# LATCHING_CIRCUITS.net
KiCad netlist of a schematic drawn in Altium Designer
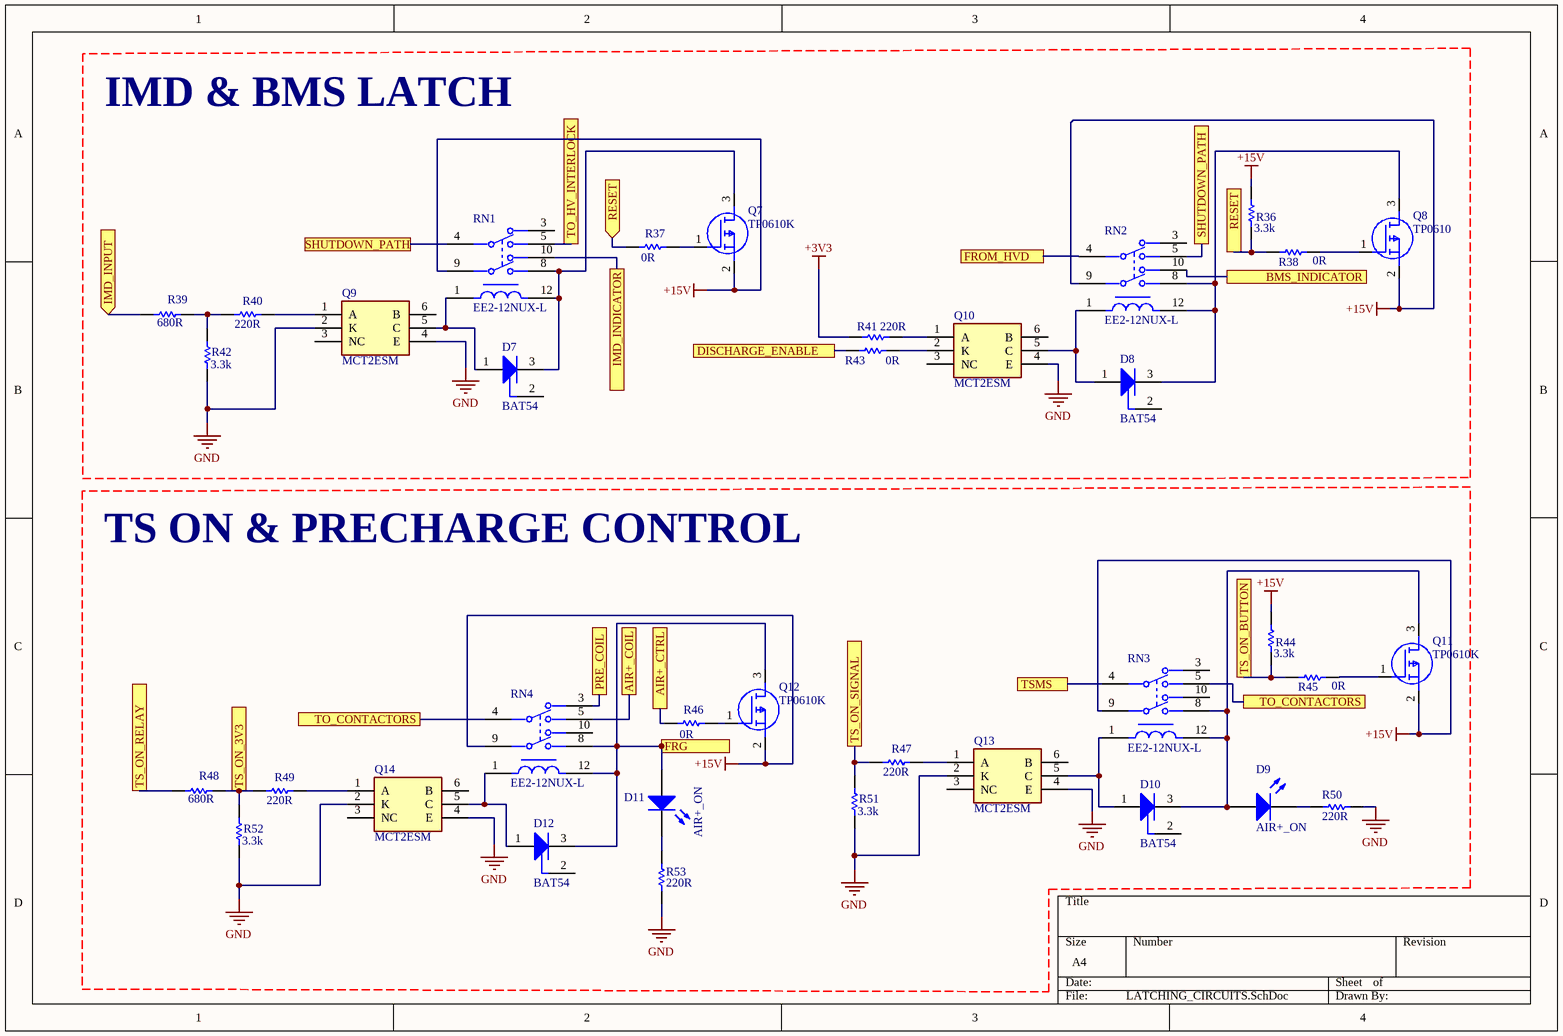
[diagram p0: LATCHING_CIRCUITS.SchDoc]

(export (version "E")
  (design (tool "Eeschema 10.0.6"))
  (components
    (comp (ref "D7")
      (value "BAT54")
      (footprint "INF-SOT23_N")
      (description "Silicon Schottky Diode, SOT23, Reel, Green")
      (fields (field (name "MANUFACTURER") "Infineon"))
      (libsource (lib "Schlib1") (part "CMP-1182-00010-1"))
    )
    (comp (ref "D8")
      (value "BAT54")
      (footprint "INF-SOT23_N")
      (description "Silicon Schottky Diode, SOT23, Reel, Green")
      (fields (field (name "MANUFACTURER") "Infineon"))
      (libsource (lib "Schlib1") (part "CMP-1182-00010-1"))
    )
    (comp (ref "D9")
      (value "AIR+_ON")
      (footprint "3.2X1.6X1.1")
      (description "Typical RED, GREEN, YELLOW, AMBER GaAs LED")
      (fields (field (name "PUBLISHER") "Altium Limited"))
      (libsource (lib "Miscellaneous Devices") (part "LED2"))
    )
    (comp (ref "D10")
      (value "BAT54")
      (footprint "INF-SOT23_N")
      (description "Silicon Schottky Diode, SOT23, Reel, Green")
      (fields (field (name "MANUFACTURER") "Infineon"))
      (libsource (lib "Schlib1") (part "CMP-1182-00010-1"))
    )
    (comp (ref "D11")
      (value "AIR+_ON")
      (footprint "3.2X1.6X1.1")
      (description "Typical RED, GREEN, YELLOW, AMBER GaAs LED")
      (fields (field (name "PUBLISHER") "Altium Limited"))
      (libsource (lib "Miscellaneous Devices") (part "LED2"))
    )
    (comp (ref "D12")
      (value "BAT54")
      (footprint "INF-SOT23_N")
      (description "Silicon Schottky Diode, SOT23, Reel, Green")
      (fields (field (name "MANUFACTURER") "Infineon"))
      (libsource (lib "Schlib1") (part "CMP-1182-00010-1"))
    )
    (comp (ref "Q7")
      (value "TP0610K")
      (footprint "SamacSys:SOT96P240X110-3N")
      (description "MOSFET (P-Channel)")
      (fields
        (field (name "MANUFACTURER_PART_NUMBER") "DMP3125L-7")
        (field (name "MOUSER PART NUMBER") "621-DMP3125L-7")
      )
      (libsource (lib "*") (part "DMP3125L-7"))
    )
    (comp (ref "Q8")
      (value "TP0610")
      (footprint "SamacSys:SOT96P240X110-3N")
      (description "MOSFET (P-Channel)")
      (fields
        (field (name "MANUFACTURER_PART_NUMBER") "DMP3125L-7")
        (field (name "MOUSER PART NUMBER") "621-DMP3125L-7")
      )
      (libsource (lib "*") (part "DMP3125L-7"))
    )
    (comp (ref "Q9")
      (value "MCT2ESM")
      (footprint "SOT254P916X480-6N")
      (description "Phototransistor")
      (fields (field (name "MOUSER PART NUMBER") "512-MCT2ESM"))
      (libsource (lib "SamacSys") (part "MCT2ESM"))
    )
    (comp (ref "Q10")
      (value "MCT2ESM")
      (footprint "SOT254P916X480-6N")
      (description "Phototransistor")
      (fields (field (name "MOUSER PART NUMBER") "512-MCT2ESM"))
      (libsource (lib "SamacSys") (part "MCT2ESM"))
    )
    (comp (ref "Q11")
      (value "TP0610K")
      (footprint "SamacSys:SOT96P240X110-3N")
      (description "MOSFET (P-Channel)")
      (fields
        (field (name "MANUFACTURER_PART_NUMBER") "DMP3125L-7")
        (field (name "MOUSER PART NUMBER") "621-DMP3125L-7")
      )
      (libsource (lib "*") (part "DMP3125L-7"))
    )
    (comp (ref "Q12")
      (value "TP0610K")
      (footprint "SamacSys:SOT96P240X110-3N")
      (description "MOSFET (P-Channel)")
      (fields
        (field (name "MANUFACTURER_PART_NUMBER") "DMP3125L-7")
        (field (name "MOUSER PART NUMBER") "621-DMP3125L-7")
      )
      (libsource (lib "*") (part "DMP3125L-7"))
    )
    (comp (ref "Q13")
      (value "MCT2ESM")
      (footprint "SOT254P916X480-6N")
      (description "Phototransistor")
      (fields (field (name "MOUSER PART NUMBER") "512-MCT2ESM"))
      (libsource (lib "SamacSys") (part "MCT2ESM"))
    )
    (comp (ref "Q14")
      (value "MCT2ESM")
      (footprint "SOT254P916X480-6N")
      (description "Phototransistor")
      (fields (field (name "MOUSER PART NUMBER") "512-MCT2ESM"))
      (libsource (lib "SamacSys") (part "MCT2ESM"))
    )
    (comp (ref "R36")
      (value "3.3k")
      (footprint "RESC3216X60X45NL10T20 - duplicate")
      (fields (field (name "PART NUMBER") "CRCW120647K0FKEA") (field (name "MANUFACTURER") "Vishay Dale"))
      (libsource (lib "Schlib1") (part "CMP-2003-02213-1"))
    )
    (comp (ref "R37")
      (value "0R")
      (footprint "RESC3216X60X45NL10T20 - duplicate")
      (fields (field (name "PART NUMBER") "CRCW120647K0FKEA") (field (name "MANUFACTURER") "Vishay Dale"))
      (libsource (lib "Schlib1") (part "CMP-2003-02213-1"))
    )
    (comp (ref "R38")
      (value "0R")
      (footprint "RESC3216X60X45NL10T20 - duplicate")
      (fields (field (name "PART NUMBER") "CRCW120647K0FKEA") (field (name "MANUFACTURER") "Vishay Dale"))
      (libsource (lib "Schlib1") (part "CMP-2003-02213-1"))
    )
    (comp (ref "R39")
      (value "680R")
      (footprint "RESC3216X60X45NL10T20 - duplicate")
      (fields (field (name "PART NUMBER") "CRCW120647K0FKEA") (field (name "MANUFACTURER") "Vishay Dale"))
      (libsource (lib "Schlib1") (part "CMP-2003-02213-1"))
    )
    (comp (ref "R40")
      (value "220R")
      (footprint "RESC3216X60X45NL10T20 - duplicate")
      (fields (field (name "PART NUMBER") "CRCW120647K0FKEA") (field (name "MANUFACTURER") "Vishay Dale"))
      (libsource (lib "Schlib1") (part "CMP-2003-02213-1"))
    )
    (comp (ref "R41")
      (value "220R")
      (footprint "RESC3216X60X45NL10T20 - duplicate")
      (fields (field (name "PART NUMBER") "CRCW120647K0FKEA") (field (name "MANUFACTURER") "Vishay Dale"))
      (libsource (lib "Schlib1") (part "CMP-2003-02213-1"))
    )
    (comp (ref "R42")
      (value "3.3k")
      (footprint "RESC3216X60X45NL10T20 - duplicate")
      (fields (field (name "PART NUMBER") "CRCW120647K0FKEA") (field (name "MANUFACTURER") "Vishay Dale"))
      (libsource (lib "Schlib1") (part "CMP-2003-02213-1"))
    )
    (comp (ref "R43")
      (value "0R")
      (footprint "RESC3216X60X45NL10T20 - duplicate")
      (fields (field (name "PART NUMBER") "CRCW120647K0FKEA") (field (name "MANUFACTURER") "Vishay Dale"))
      (libsource (lib "Schlib1") (part "CMP-2003-02213-1"))
    )
    (comp (ref "R44")
      (value "3.3k")
      (footprint "RESC3216X60X45NL10T20 - duplicate")
      (fields (field (name "PART NUMBER") "CRCW120647K0FKEA") (field (name "MANUFACTURER") "Vishay Dale"))
      (libsource (lib "Schlib1") (part "CMP-2003-02213-1"))
    )
    (comp (ref "R45")
      (value "0R")
      (footprint "RESC3216X60X45NL10T20 - duplicate")
      (fields (field (name "PART NUMBER") "CRCW120647K0FKEA") (field (name "MANUFACTURER") "Vishay Dale"))
      (libsource (lib "Schlib1") (part "CMP-2003-02213-1"))
    )
    (comp (ref "R46")
      (value "0R")
      (footprint "RESC3216X60X45NL10T20 - duplicate")
      (fields (field (name "PART NUMBER") "CRCW120647K0FKEA") (field (name "MANUFACTURER") "Vishay Dale"))
      (libsource (lib "Schlib1") (part "CMP-2003-02213-1"))
    )
    (comp (ref "R47")
      (value "220R")
      (footprint "RESC3216X60X45NL10T20 - duplicate")
      (fields (field (name "PART NUMBER") "CRCW120647K0FKEA") (field (name "MANUFACTURER") "Vishay Dale"))
      (libsource (lib "Schlib1") (part "CMP-2003-02213-1"))
    )
    (comp (ref "R48")
      (value "680R")
      (footprint "RESC3216X60X45NL10T20 - duplicate")
      (fields (field (name "PART NUMBER") "CRCW120647K0FKEA") (field (name "MANUFACTURER") "Vishay Dale"))
      (libsource (lib "Schlib1") (part "CMP-2003-02213-1"))
    )
    (comp (ref "R49")
      (value "220R")
      (footprint "RESC3216X60X45NL10T20 - duplicate")
      (fields (field (name "PART NUMBER") "CRCW120647K0FKEA") (field (name "MANUFACTURER") "Vishay Dale"))
      (libsource (lib "Schlib1") (part "CMP-2003-02213-1"))
    )
    (comp (ref "R50")
      (value "220R")
      (footprint "RESC3216X60X45NL10T20 - duplicate")
      (fields (field (name "PART NUMBER") "CRCW120647K0FKEA") (field (name "MANUFACTURER") "Vishay Dale"))
      (libsource (lib "Regular_used_components_2D_Symbol") (part "CMP-2003-02213-1"))
    )
    (comp (ref "R51")
      (value "3.3k")
      (footprint "RESC3216X60X45NL10T20 - duplicate")
      (fields (field (name "PART NUMBER") "CRCW120647K0FKEA") (field (name "MANUFACTURER") "Vishay Dale"))
      (libsource (lib "Schlib1") (part "CMP-2003-02213-1"))
    )
    (comp (ref "R52")
      (value "3.3k")
      (footprint "RESC3216X60X45NL10T20 - duplicate")
      (fields (field (name "PART NUMBER") "CRCW120647K0FKEA") (field (name "MANUFACTURER") "Vishay Dale"))
      (libsource (lib "Schlib1") (part "CMP-2003-02213-1"))
    )
    (comp (ref "R53")
      (value "220R")
      (footprint "RESC3216X60X45NL10T20 - duplicate")
      (fields (field (name "PART NUMBER") "CRCW120647K0FKEA") (field (name "MANUFACTURER") "Vishay Dale"))
      (libsource (lib "Regular_used_components_2D_Symbol") (part "CMP-2003-02213-1"))
    )
    (comp (ref "RN1")
      (value "EE2-12NUX-L")
      (footprint "EE2-12NUX-L")
      (libsource (lib "Schlib1") (part "EE2-12NUX-L"))
    )
    (comp (ref "RN2")
      (value "EE2-12NUX-L")
      (footprint "EE2-12NUX-L")
      (libsource (lib "Schlib1") (part "EE2-12NUX-L"))
    )
    (comp (ref "RN3")
      (value "EE2-12NUX-L")
      (footprint "EE2-12NUX-L")
      (libsource (lib "Schlib1") (part "EE2-12NUX-L"))
    )
    (comp (ref "RN4")
      (value "EE2-12NUX-L")
      (footprint "EE2-12NUX-L")
      (libsource (lib "Schlib1") (part "EE2-12NUX-L"))
    )
  )
  (nets
    (net (code "1") (name "+3V3") (class "Default")
      (node (ref "R41") (pin "2") (pinfunction "2_2") (pintype "passive"))
    )
    (net (code "2") (name "+15V") (class "Default")
      (node (ref "Q11") (pin "2") (pinfunction "S_2") (pintype "passive"))
      (node (ref "Q12") (pin "2") (pinfunction "S_2") (pintype "passive"))
      (node (ref "Q7") (pin "2") (pinfunction "S_2") (pintype "passive"))
      (node (ref "Q8") (pin "2") (pinfunction "S_2") (pintype "passive"))
      (node (ref "R36") (pin "2") (pinfunction "2_2") (pintype "passive"))
      (node (ref "R44") (pin "2") (pinfunction "2_2") (pintype "passive"))
      (node (ref "RN1") (pin "9") (pinfunction "9_9") (pintype "passive"))
      (node (ref "RN2") (pin "9") (pinfunction "9_9") (pintype "passive"))
      (node (ref "RN3") (pin "9") (pinfunction "9_9") (pintype "passive"))
      (node (ref "RN4") (pin "9") (pinfunction "9_9") (pintype "passive"))
    )
    (net (code "3") (name "/AIR+_COIL") (class "Default")
      (node (ref "RN4") (pin "5") (pinfunction "5_5") (pintype "passive"))
    )
    (net (code "4") (name "/AIR+_CTRL") (class "Default")
      (node (ref "R46") (pin "2") (pinfunction "2_2") (pintype "passive"))
    )
    (net (code "5") (name "/BMS_INDICATOR") (class "Default")
      (node (ref "RN2") (pin "10") (pinfunction "10_10") (pintype "passive"))
    )
    (net (code "6") (name "/DISCHARGE_ENABLE") (class "Default")
      (node (ref "R43") (pin "2") (pinfunction "2_2") (pintype "passive"))
    )
    (net (code "7") (name "/FRG") (class "Default")
      (node (ref "D11") (pin "1") (pinfunction "A_1") (pintype "passive"))
      (node (ref "D12") (pin "3") (pinfunction "K_3") (pintype "passive"))
      (node (ref "Q12") (pin "3") (pinfunction "D_3") (pintype "passive"))
      (node (ref "RN4") (pin "12") (pinfunction "12_12") (pintype "passive"))
      (node (ref "RN4") (pin "8") (pinfunction "8_8") (pintype "passive"))
    )
    (net (code "8") (name "/FROM_HVD") (class "Default")
      (node (ref "RN2") (pin "4") (pinfunction "4_4") (pintype "passive"))
    )
    (net (code "9") (name "/IMD_INDICATOR") (class "Default")
      (node (ref "RN1") (pin "10") (pinfunction "10_10") (pintype "passive"))
    )
    (net (code "10") (name "/IMD_INPUT") (class "Default")
      (node (ref "R39") (pin "2") (pinfunction "2_2") (pintype "passive"))
    )
    (net (code "11") (name "/PRE_COIL") (class "Default")
      (node (ref "RN4") (pin "3") (pinfunction "3_3") (pintype "passive"))
    )
    (net (code "12") (name "/RESET") (class "Default")
      (node (ref "R36") (pin "1") (pinfunction "1_1") (pintype "passive"))
      (node (ref "R37") (pin "2") (pinfunction "2_2") (pintype "passive"))
      (node (ref "R38") (pin "2") (pinfunction "2_2") (pintype "passive"))
    )
    (net (code "13") (name "/SHUTDOWN_PATH") (class "Default")
      (node (ref "RN1") (pin "4") (pinfunction "4_4") (pintype "passive"))
      (node (ref "RN2") (pin "5") (pinfunction "5_5") (pintype "passive"))
    )
    (net (code "14") (name "/TO_CONTACTORS") (class "Default")
      (node (ref "RN3") (pin "5") (pinfunction "5_5") (pintype "passive"))
      (node (ref "RN4") (pin "4") (pinfunction "4_4") (pintype "passive"))
    )
    (net (code "15") (name "/TO_HV_INTERLOCK") (class "Default")
      (node (ref "RN1") (pin "5") (pinfunction "5_5") (pintype "passive"))
    )
    (net (code "16") (name "/TSMS") (class "Default")
      (node (ref "RN3") (pin "4") (pinfunction "4_4") (pintype "passive"))
    )
    (net (code "17") (name "/TS_ON_3V3") (class "Default")
      (node (ref "R48") (pin "1") (pinfunction "1_1") (pintype "passive"))
      (node (ref "R49") (pin "2") (pinfunction "2_2") (pintype "passive"))
      (node (ref "R52") (pin "2") (pinfunction "2_2") (pintype "passive"))
    )
    (net (code "18") (name "/TS_ON_BUTTON") (class "Default")
      (node (ref "R44") (pin "1") (pinfunction "1_1") (pintype "passive"))
      (node (ref "R45") (pin "2") (pinfunction "2_2") (pintype "passive"))
    )
    (net (code "19") (name "/TS_ON_RELAY") (class "Default")
      (node (ref "R48") (pin "2") (pinfunction "2_2") (pintype "passive"))
    )
    (net (code "20") (name "/TS_ON_SIGNAL") (class "Default")
      (node (ref "R47") (pin "2") (pinfunction "2_2") (pintype "passive"))
      (node (ref "R51") (pin "2") (pinfunction "2_2") (pintype "passive"))
    )
    (net (code "21") (name "GND") (class "Default")
      (node (ref "Q10") (pin "4") (pinfunction "E_4") (pintype "passive"))
      (node (ref "Q13") (pin "2") (pinfunction "K_2") (pintype "passive"))
      (node (ref "Q13") (pin "4") (pinfunction "E_4") (pintype "passive"))
      (node (ref "Q14") (pin "2") (pinfunction "K_2") (pintype "passive"))
      (node (ref "Q14") (pin "4") (pinfunction "E_4") (pintype "passive"))
      (node (ref "Q9") (pin "2") (pinfunction "K_2") (pintype "passive"))
      (node (ref "Q9") (pin "4") (pinfunction "E_4") (pintype "passive"))
      (node (ref "R42") (pin "1") (pinfunction "1_1") (pintype "passive"))
      (node (ref "R50") (pin "1") (pinfunction "1_1") (pintype "passive"))
      (node (ref "R51") (pin "1") (pinfunction "1_1") (pintype "passive"))
      (node (ref "R52") (pin "1") (pinfunction "1_1") (pintype "passive"))
      (node (ref "R53") (pin "1") (pinfunction "1_1") (pintype "passive"))
    )
    (net (code "22") (name "Net-(D7-A)") (class "Default")
      (node (ref "D7") (pin "1") (pinfunction "A_1") (pintype "passive"))
      (node (ref "Q9") (pin "5") (pinfunction "C_5") (pintype "passive"))
      (node (ref "RN1") (pin "1") (pinfunction "1_1") (pintype "passive"))
    )
    (net (code "23") (name "Net-(D7-K)") (class "Default")
      (node (ref "D7") (pin "3") (pinfunction "K_3") (pintype "passive"))
      (node (ref "Q7") (pin "3") (pinfunction "D_3") (pintype "passive"))
      (node (ref "RN1") (pin "12") (pinfunction "12_12") (pintype "passive"))
      (node (ref "RN1") (pin "8") (pinfunction "8_8") (pintype "passive"))
    )
    (net (code "24") (name "Net-(D8-A)") (class "Default")
      (node (ref "D8") (pin "1") (pinfunction "A_1") (pintype "passive"))
      (node (ref "Q10") (pin "5") (pinfunction "C_5") (pintype "passive"))
      (node (ref "RN2") (pin "1") (pinfunction "1_1") (pintype "passive"))
    )
    (net (code "25") (name "Net-(D8-K)") (class "Default")
      (node (ref "D8") (pin "3") (pinfunction "K_3") (pintype "passive"))
      (node (ref "Q8") (pin "3") (pinfunction "D_3") (pintype "passive"))
      (node (ref "RN2") (pin "12") (pinfunction "12_12") (pintype "passive"))
      (node (ref "RN2") (pin "8") (pinfunction "8_8") (pintype "passive"))
    )
    (net (code "26") (name "Net-(D9-K)") (class "Default")
      (node (ref "D9") (pin "2") (pinfunction "K_2") (pintype "passive"))
      (node (ref "R50") (pin "2") (pinfunction "2_2") (pintype "passive"))
    )
    (net (code "27") (name "Net-(D10-A)") (class "Default")
      (node (ref "D10") (pin "1") (pinfunction "A_1") (pintype "passive"))
      (node (ref "Q13") (pin "5") (pinfunction "C_5") (pintype "passive"))
      (node (ref "RN3") (pin "1") (pinfunction "1_1") (pintype "passive"))
    )
    (net (code "28") (name "Net-(D10-K)") (class "Default")
      (node (ref "D10") (pin "3") (pinfunction "K_3") (pintype "passive"))
      (node (ref "D9") (pin "1") (pinfunction "A_1") (pintype "passive"))
      (node (ref "Q11") (pin "3") (pinfunction "D_3") (pintype "passive"))
      (node (ref "RN3") (pin "12") (pinfunction "12_12") (pintype "passive"))
      (node (ref "RN3") (pin "8") (pinfunction "8_8") (pintype "passive"))
    )
    (net (code "29") (name "Net-(D11-K)") (class "Default")
      (node (ref "D11") (pin "2") (pinfunction "K_2") (pintype "passive"))
      (node (ref "R53") (pin "2") (pinfunction "2_2") (pintype "passive"))
    )
    (net (code "30") (name "Net-(D12-A)") (class "Default")
      (node (ref "D12") (pin "1") (pinfunction "A_1") (pintype "passive"))
      (node (ref "Q14") (pin "5") (pinfunction "C_5") (pintype "passive"))
      (node (ref "RN4") (pin "1") (pinfunction "1_1") (pintype "passive"))
    )
    (net (code "31") (name "Net-(Q7-G)") (class "Default")
      (node (ref "Q7") (pin "1") (pinfunction "G_1") (pintype "passive"))
      (node (ref "R37") (pin "1") (pinfunction "1_1") (pintype "passive"))
    )
    (net (code "32") (name "Net-(Q8-G)") (class "Default")
      (node (ref "Q8") (pin "1") (pinfunction "G_1") (pintype "passive"))
      (node (ref "R38") (pin "1") (pinfunction "1_1") (pintype "passive"))
    )
    (net (code "33") (name "Net-(Q9-A)") (class "Default")
      (node (ref "Q9") (pin "1") (pinfunction "A_1") (pintype "passive"))
      (node (ref "R40") (pin "1") (pinfunction "1_1") (pintype "passive"))
    )
    (net (code "34") (name "Net-(Q10-A)") (class "Default")
      (node (ref "Q10") (pin "1") (pinfunction "A_1") (pintype "passive"))
      (node (ref "R41") (pin "1") (pinfunction "1_1") (pintype "passive"))
    )
    (net (code "35") (name "Net-(Q10-K)") (class "Default")
      (node (ref "Q10") (pin "2") (pinfunction "K_2") (pintype "passive"))
      (node (ref "R43") (pin "1") (pinfunction "1_1") (pintype "passive"))
    )
    (net (code "36") (name "Net-(Q11-G)") (class "Default")
      (node (ref "Q11") (pin "1") (pinfunction "G_1") (pintype "passive"))
      (node (ref "R45") (pin "1") (pinfunction "1_1") (pintype "passive"))
    )
    (net (code "37") (name "Net-(Q12-G)") (class "Default")
      (node (ref "Q12") (pin "1") (pinfunction "G_1") (pintype "passive"))
      (node (ref "R46") (pin "1") (pinfunction "1_1") (pintype "passive"))
    )
    (net (code "38") (name "Net-(Q13-A)") (class "Default")
      (node (ref "Q13") (pin "1") (pinfunction "A_1") (pintype "passive"))
      (node (ref "R47") (pin "1") (pinfunction "1_1") (pintype "passive"))
    )
    (net (code "39") (name "Net-(Q14-A)") (class "Default")
      (node (ref "Q14") (pin "1") (pinfunction "A_1") (pintype "passive"))
      (node (ref "R49") (pin "1") (pinfunction "1_1") (pintype "passive"))
    )
    (net (code "40") (name "Net-(R39-Pad1)") (class "Default")
      (node (ref "R39") (pin "1") (pinfunction "1_1") (pintype "passive"))
      (node (ref "R40") (pin "2") (pinfunction "2_2") (pintype "passive"))
      (node (ref "R42") (pin "2") (pinfunction "2_2") (pintype "passive"))
    )
    (net (code "41") (name "unconnected-(D7-NC-Pad2)") (class "Default")
      (node (ref "D7") (pin "2") (pinfunction "NC_2") (pintype "passive"))
    )
    (net (code "42") (name "unconnected-(D8-NC-Pad2)") (class "Default")
      (node (ref "D8") (pin "2") (pinfunction "NC_2") (pintype "passive"))
    )
    (net (code "43") (name "unconnected-(D10-NC-Pad2)") (class "Default")
      (node (ref "D10") (pin "2") (pinfunction "NC_2") (pintype "passive"))
    )
    (net (code "44") (name "unconnected-(D12-NC-Pad2)") (class "Default")
      (node (ref "D12") (pin "2") (pinfunction "NC_2") (pintype "passive"))
    )
    (net (code "45") (name "unconnected-(Q9-B-Pad6)") (class "Default")
      (node (ref "Q9") (pin "6") (pinfunction "B_6") (pintype "passive"))
    )
    (net (code "46") (name "unconnected-(Q9-NC-Pad3)") (class "Default")
      (node (ref "Q9") (pin "3") (pinfunction "NC_3") (pintype "passive"))
    )
    (net (code "47") (name "unconnected-(Q10-B-Pad6)") (class "Default")
      (node (ref "Q10") (pin "6") (pinfunction "B_6") (pintype "passive"))
    )
    (net (code "48") (name "unconnected-(Q10-NC-Pad3)") (class "Default")
      (node (ref "Q10") (pin "3") (pinfunction "NC_3") (pintype "passive"))
    )
    (net (code "49") (name "unconnected-(Q13-B-Pad6)") (class "Default")
      (node (ref "Q13") (pin "6") (pinfunction "B_6") (pintype "passive"))
    )
    (net (code "50") (name "unconnected-(Q13-NC-Pad3)") (class "Default")
      (node (ref "Q13") (pin "3") (pinfunction "NC_3") (pintype "passive"))
    )
    (net (code "51") (name "unconnected-(Q14-B-Pad6)") (class "Default")
      (node (ref "Q14") (pin "6") (pinfunction "B_6") (pintype "passive"))
    )
    (net (code "52") (name "unconnected-(Q14-NC-Pad3)") (class "Default")
      (node (ref "Q14") (pin "3") (pinfunction "NC_3") (pintype "passive"))
    )
    (net (code "53") (name "unconnected-(RN1-Pad3)") (class "Default")
      (node (ref "RN1") (pin "3") (pinfunction "3_3") (pintype "passive"))
    )
    (net (code "54") (name "unconnected-(RN2-Pad3)") (class "Default")
      (node (ref "RN2") (pin "3") (pinfunction "3_3") (pintype "passive"))
    )
    (net (code "55") (name "unconnected-(RN3-Pad3)") (class "Default")
      (node (ref "RN3") (pin "3") (pinfunction "3_3") (pintype "passive"))
    )
    (net (code "56") (name "unconnected-(RN3-Pad10)") (class "Default")
      (node (ref "RN3") (pin "10") (pinfunction "10_10") (pintype "passive"))
    )
    (net (code "57") (name "unconnected-(RN4-Pad10)") (class "Default")
      (node (ref "RN4") (pin "10") (pinfunction "10_10") (pintype "passive"))
    )
  )
)
